# v2_0_Door.net
KiCad netlist of a schematic drawn in EAGLE
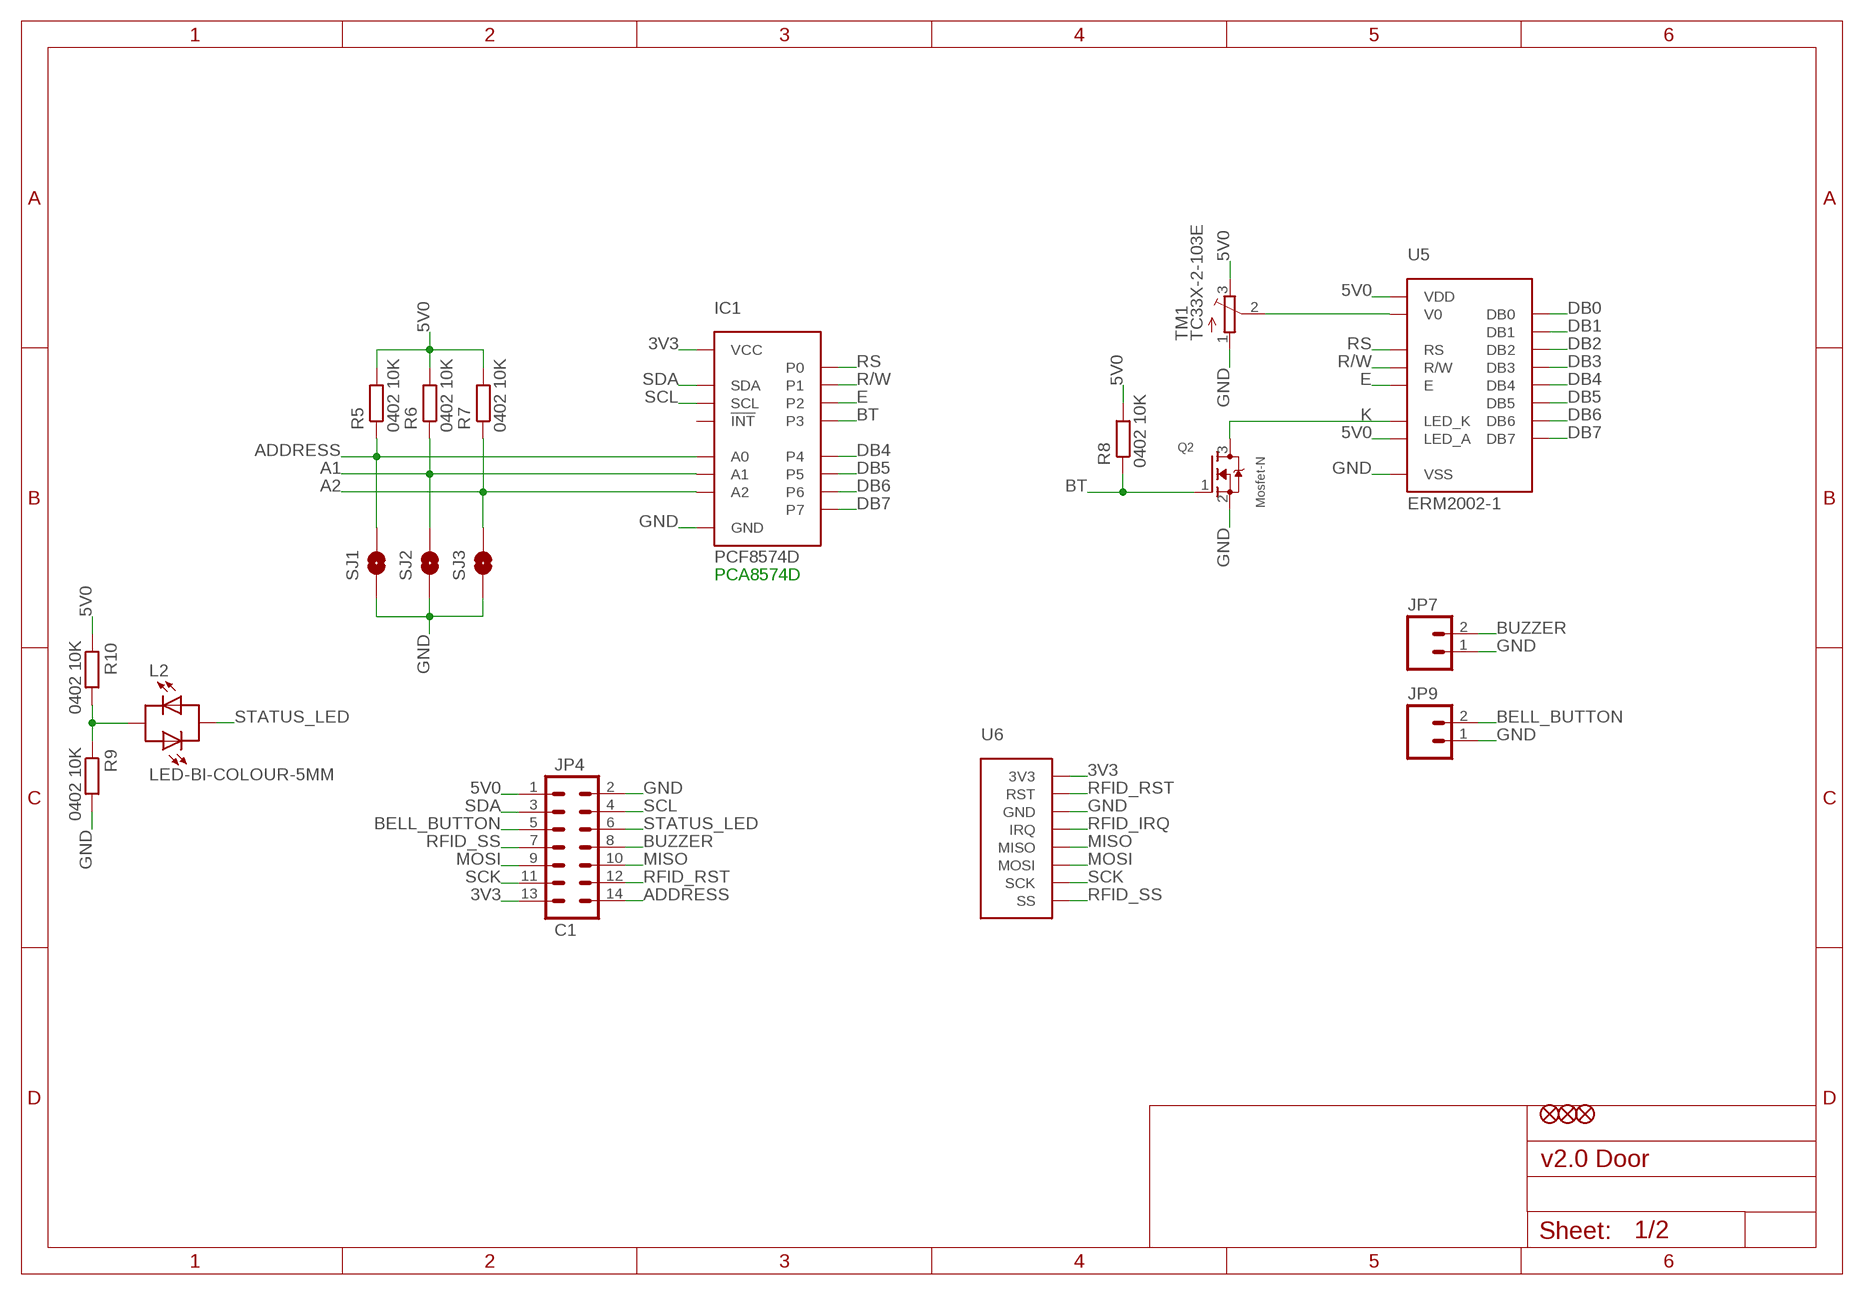
[diagram p0: schematic, sheet 1]
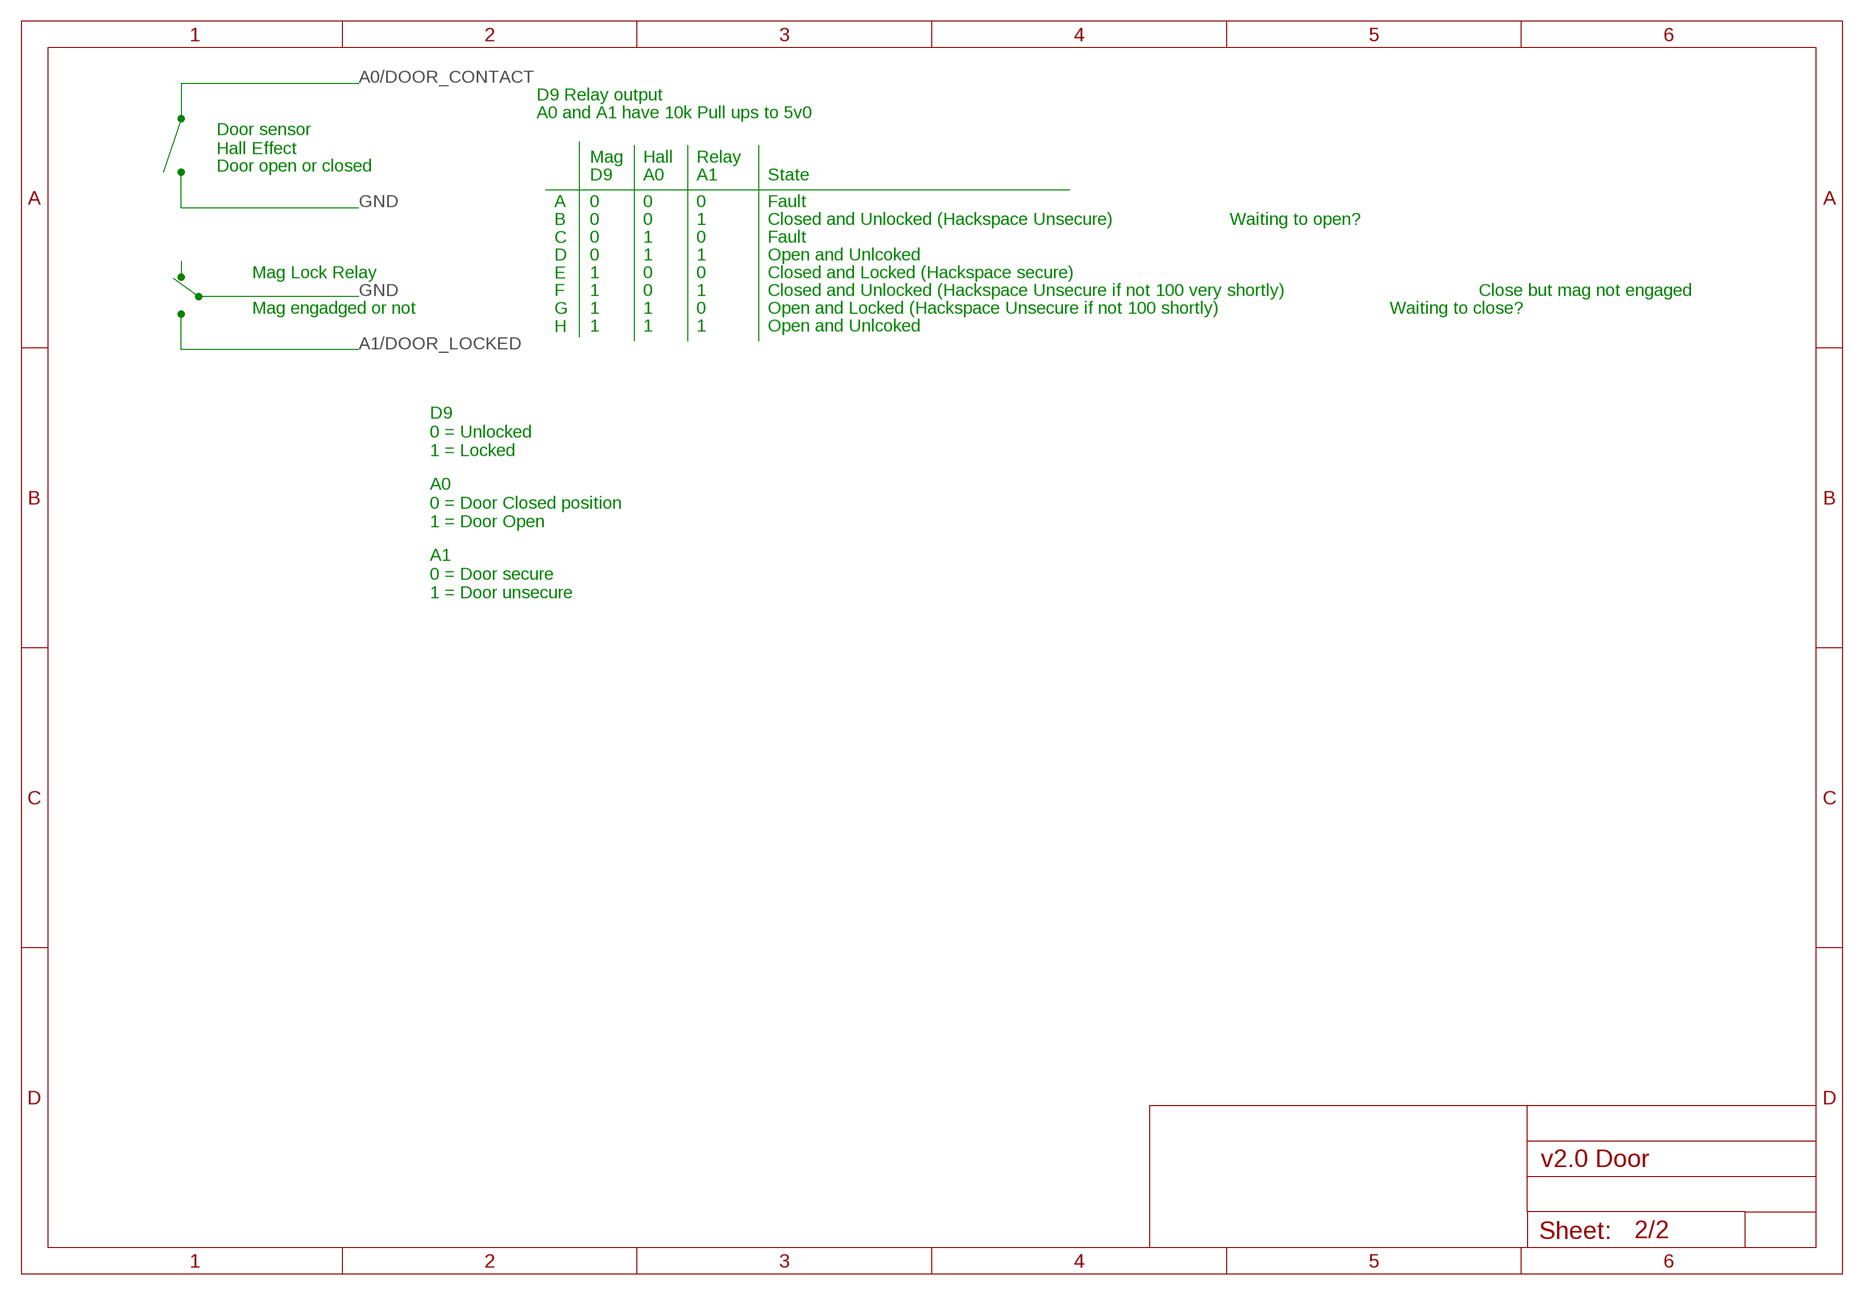
[diagram p1: schematic, sheet 2]

(export (version "E")
  (design (tool "Eeschema 10.0.6"))
  (components
    (comp (ref "IC1")
      (value "PCF8574D")
      (footprint "eagle-import:SO16")
      (libsource (lib "eagle-import") (part "PCF8574"))
    )
    (comp (ref "JP1")
      (value "FIDUCIAL1X2.5-STOP")
      (footprint "eagle-import:FIDUCIAL-1X2.5-STOP")
      (libsource (lib "eagle-import") (part "FIDUCIAL1X2.5-STOP"))
    )
    (comp (ref "JP2")
      (value "FIDUCIAL1X2.5-STOP")
      (footprint "eagle-import:FIDUCIAL-1X2.5-STOP")
      (libsource (lib "eagle-import") (part "FIDUCIAL1X2.5-STOP"))
    )
    (comp (ref "JP3")
      (value "FIDUCIAL1X2.5-STOP")
      (footprint "eagle-import:FIDUCIAL-1X2.5-STOP")
      (libsource (lib "eagle-import") (part "FIDUCIAL1X2.5-STOP"))
    )
    (comp (ref "JP4")
      (value "C1")
      (footprint "eagle-import:2X7-SHROUDED_LOCK")
      (libsource (lib "eagle-import") (part "M07X2-SHOROUDED_LOCK"))
    )
    (comp (ref "JP7")
      (value "M02POLAR_LOCK")
      (footprint "eagle-import:MOLEX-1X2_LOCK")
      (libsource (lib "eagle-import") (part "M02POLAR_LOCK"))
    )
    (comp (ref "JP9")
      (value "M02POLAR_LOCK")
      (footprint "eagle-import:MOLEX-1X2_LOCK")
      (libsource (lib "eagle-import") (part "M02POLAR_LOCK"))
    )
    (comp (ref "L2")
      (value "LED-BI-COLOUR-5MM")
      (footprint "eagle-import:LED5MM")
      (libsource (lib "eagle-import") (part "LED-BI-COLOUR-5MM"))
    )
    (comp (ref "Q2")
      (value "Mosfet-N")
      (footprint "eagle-import:SOT23-3")
      (libsource (lib "eagle-import") (part "MOSFET-N-SOT23-SPARK"))
    )
    (comp (ref "R5")
      (value "0402 10K")
      (footprint "eagle-import:R0402-SMALLER")
      (libsource (lib "eagle-import") (part "R-EU_R0402-SMALLER"))
    )
    (comp (ref "R6")
      (value "0402 10K")
      (footprint "eagle-import:R0402-SMALLER")
      (libsource (lib "eagle-import") (part "R-EU_R0402-SMALLER"))
    )
    (comp (ref "R7")
      (value "0402 10K")
      (footprint "eagle-import:R0402-SMALLER")
      (libsource (lib "eagle-import") (part "R-EU_R0402-SMALLER"))
    )
    (comp (ref "R8")
      (value "0402 10K")
      (footprint "eagle-import:R0402-SMALLER")
      (libsource (lib "eagle-import") (part "R-EU_R0402-SMALLER"))
    )
    (comp (ref "R9")
      (value "0402 10K")
      (footprint "eagle-import:R0402-SMALLER")
      (libsource (lib "eagle-import") (part "R-EU_R0402-SMALLER"))
    )
    (comp (ref "R10")
      (value "0402 10K")
      (footprint "eagle-import:R0402-SMALLER")
      (libsource (lib "eagle-import") (part "R-EU_R0402-SMALLER"))
    )
    (comp (ref "SJ1")
      (value "SOLDERJUMPERNO")
      (footprint "eagle-import:SJ_2S-NO")
      (libsource (lib "eagle-import") (part "SOLDERJUMPERNO"))
    )
    (comp (ref "SJ2")
      (value "SOLDERJUMPERNO")
      (footprint "eagle-import:SJ_2S-NO")
      (libsource (lib "eagle-import") (part "SOLDERJUMPERNO"))
    )
    (comp (ref "SJ3")
      (value "SOLDERJUMPERNO")
      (footprint "eagle-import:SJ_2S-NO")
      (libsource (lib "eagle-import") (part "SOLDERJUMPERNO"))
    )
    (comp (ref "TM1")
      (value "TC33X-2-103E")
      (footprint "eagle-import:TC33X")
      (libsource (lib "eagle-import") (part "TRIMPOTTC33X"))
    )
    (comp (ref "U5")
      (value "ERM2002-1")
      (footprint "eagle-import:ERM2002-1-GATEKEEPER")
      (libsource (lib "eagle-import") (part "ERM2002-1-GATEKEEPER"))
    )
    (comp (ref "U6")
      (value "RFID-RC522-GATEKEEPER")
      (footprint "eagle-import:RFID-RC522-GATEKEEPER")
      (libsource (lib "eagle-import") (part "RFID-RC522-GATEKEEPER"))
    )
  )
  (nets
    (net (code "1") (name "3V3") (class "Default")
      (node (ref "IC1") (pin "16") (pinfunction "VCC_16") (pintype "bidirectional"))
      (node (ref "JP4") (pin "13") (pinfunction "13_13") (pintype "passive"))
      (node (ref "U6") (pin "8") (pinfunction "3V3_8") (pintype "bidirectional"))
    )
    (net (code "2") (name "5V0") (class "Default")
      (node (ref "JP4") (pin "1") (pinfunction "1_1") (pintype "passive"))
      (node (ref "R10") (pin "1") (pinfunction "1_1") (pintype "passive"))
      (node (ref "R5") (pin "2") (pinfunction "2_2") (pintype "passive"))
      (node (ref "R6") (pin "2") (pinfunction "2_2") (pintype "passive"))
      (node (ref "R7") (pin "2") (pinfunction "2_2") (pintype "passive"))
      (node (ref "R8") (pin "2") (pinfunction "2_2") (pintype "passive"))
      (node (ref "TM1") (pin "3") (pinfunction "E_3") (pintype "passive"))
      (node (ref "U5") (pin "15") (pinfunction "LED_A_15") (pintype "bidirectional"))
      (node (ref "U5") (pin "2") (pinfunction "VDD_2") (pintype "bidirectional"))
    )
    (net (code "4") (name "A1") (class "Default")
      (node (ref "IC1") (pin "2") (pinfunction "A1_2") (pintype "bidirectional"))
      (node (ref "R6") (pin "1") (pinfunction "1_1") (pintype "passive"))
      (node (ref "SJ2") (pin "2") (pinfunction "2_2") (pintype "passive"))
    )
    (net (code "6") (name "A2") (class "Default")
      (node (ref "IC1") (pin "3") (pinfunction "A2_3") (pintype "bidirectional"))
      (node (ref "R7") (pin "1") (pinfunction "1_1") (pintype "passive"))
      (node (ref "SJ3") (pin "2") (pinfunction "2_2") (pintype "passive"))
    )
    (net (code "7") (name "ADDRESS") (class "Default")
      (node (ref "IC1") (pin "1") (pinfunction "A0_1") (pintype "bidirectional"))
      (node (ref "JP4") (pin "14") (pinfunction "14_14") (pintype "passive"))
      (node (ref "R5") (pin "1") (pinfunction "1_1") (pintype "passive"))
      (node (ref "SJ1") (pin "2") (pinfunction "2_2") (pintype "passive"))
    )
    (net (code "8") (name "BELL_BUTTON") (class "Default")
      (node (ref "JP4") (pin "5") (pinfunction "5_5") (pintype "passive"))
      (node (ref "JP9") (pin "2") (pinfunction "2_2") (pintype "passive"))
    )
    (net (code "9") (name "BT") (class "Default")
      (node (ref "IC1") (pin "7") (pinfunction "P3_7") (pintype "bidirectional"))
      (node (ref "Q2") (pin "1") (pinfunction "G_1") (pintype "bidirectional"))
      (node (ref "R8") (pin "1") (pinfunction "1_1") (pintype "passive"))
    )
    (net (code "10") (name "BUZZER") (class "Default")
      (node (ref "JP4") (pin "8") (pinfunction "8_8") (pintype "passive"))
      (node (ref "JP7") (pin "2") (pinfunction "2_2") (pintype "passive"))
    )
    (net (code "11") (name "DB0") (class "Default")
      (node (ref "U5") (pin "7") (pinfunction "DB0_7") (pintype "bidirectional"))
    )
    (net (code "12") (name "DB1") (class "Default")
      (node (ref "U5") (pin "8") (pinfunction "DB1_8") (pintype "bidirectional"))
    )
    (net (code "13") (name "DB2") (class "Default")
      (node (ref "U5") (pin "9") (pinfunction "DB2_9") (pintype "bidirectional"))
    )
    (net (code "14") (name "DB3") (class "Default")
      (node (ref "U5") (pin "10") (pinfunction "DB3_10") (pintype "bidirectional"))
    )
    (net (code "15") (name "DB4") (class "Default")
      (node (ref "IC1") (pin "9") (pinfunction "P4_9") (pintype "bidirectional"))
      (node (ref "U5") (pin "11") (pinfunction "DB4_11") (pintype "bidirectional"))
    )
    (net (code "16") (name "DB5") (class "Default")
      (node (ref "IC1") (pin "10") (pinfunction "P5_10") (pintype "bidirectional"))
      (node (ref "U5") (pin "12") (pinfunction "DB5_12") (pintype "bidirectional"))
    )
    (net (code "17") (name "DB6") (class "Default")
      (node (ref "IC1") (pin "11") (pinfunction "P6_11") (pintype "bidirectional"))
      (node (ref "U5") (pin "13") (pinfunction "DB6_13") (pintype "bidirectional"))
    )
    (net (code "18") (name "DB7") (class "Default")
      (node (ref "IC1") (pin "12") (pinfunction "P7_12") (pintype "bidirectional"))
      (node (ref "U5") (pin "14") (pinfunction "DB7_14") (pintype "bidirectional"))
    )
    (net (code "19") (name "E") (class "Default")
      (node (ref "IC1") (pin "6") (pinfunction "P2_6") (pintype "bidirectional"))
      (node (ref "U5") (pin "6") (pinfunction "E_6") (pintype "bidirectional"))
    )
    (net (code "20") (name "GND") (class "Default")
      (node (ref "IC1") (pin "8") (pinfunction "GND_8") (pintype "bidirectional"))
      (node (ref "JP4") (pin "2") (pinfunction "2_2") (pintype "passive"))
      (node (ref "JP7") (pin "1") (pinfunction "1_1") (pintype "passive"))
      (node (ref "JP9") (pin "1") (pinfunction "1_1") (pintype "passive"))
      (node (ref "Q2") (pin "2") (pinfunction "S_2") (pintype "bidirectional"))
      (node (ref "R9") (pin "2") (pinfunction "2_2") (pintype "passive"))
      (node (ref "SJ1") (pin "1") (pinfunction "1_1") (pintype "passive"))
      (node (ref "SJ2") (pin "1") (pinfunction "1_1") (pintype "passive"))
      (node (ref "SJ3") (pin "1") (pinfunction "1_1") (pintype "passive"))
      (node (ref "TM1") (pin "1") (pinfunction "A_1") (pintype "passive"))
      (node (ref "U5") (pin "1") (pinfunction "VSS_1") (pintype "bidirectional"))
      (node (ref "U6") (pin "6") (pinfunction "GND_6") (pintype "bidirectional"))
    )
    (net (code "21") (name "K") (class "Default")
      (node (ref "Q2") (pin "3") (pinfunction "D_3") (pintype "bidirectional"))
      (node (ref "U5") (pin "16") (pinfunction "LED_K_16") (pintype "bidirectional"))
    )
    (net (code "22") (name "MISO") (class "Default")
      (node (ref "JP4") (pin "10") (pinfunction "10_10") (pintype "passive"))
      (node (ref "U6") (pin "4") (pinfunction "MISO_4") (pintype "bidirectional"))
    )
    (net (code "23") (name "MOSI") (class "Default")
      (node (ref "JP4") (pin "9") (pinfunction "9_9") (pintype "passive"))
      (node (ref "U6") (pin "3") (pinfunction "MOSI_3") (pintype "bidirectional"))
    )
    (net (code "25") (name "Net-(L2-1)") (class "Default")
      (node (ref "L2") (pin "A") (pinfunction "1_A") (pintype "passive"))
      (node (ref "R10") (pin "2") (pinfunction "2_2") (pintype "passive"))
      (node (ref "R9") (pin "1") (pinfunction "1_1") (pintype "passive"))
    )
    (net (code "26") (name "Net-(TM1-S)") (class "Default")
      (node (ref "TM1") (pin "2") (pinfunction "S_2") (pintype "passive"))
      (node (ref "U5") (pin "3") (pinfunction "V0_3") (pintype "bidirectional"))
    )
    (net (code "27") (name "RFID_IRQ") (class "Default")
      (node (ref "U6") (pin "5") (pinfunction "IRQ_5") (pintype "bidirectional"))
    )
    (net (code "28") (name "RFID_RST") (class "Default")
      (node (ref "JP4") (pin "12") (pinfunction "12_12") (pintype "passive"))
      (node (ref "U6") (pin "7") (pinfunction "RST_7") (pintype "bidirectional"))
    )
    (net (code "29") (name "RFID_SS") (class "Default")
      (node (ref "JP4") (pin "7") (pinfunction "7_7") (pintype "passive"))
      (node (ref "U6") (pin "1") (pinfunction "SS_1") (pintype "bidirectional"))
    )
    (net (code "30") (name "RS") (class "Default")
      (node (ref "IC1") (pin "4") (pinfunction "P0_4") (pintype "bidirectional"))
      (node (ref "U5") (pin "4") (pinfunction "RS_4") (pintype "bidirectional"))
    )
    (net (code "31") (name "R{slash}W") (class "Default")
      (node (ref "IC1") (pin "5") (pinfunction "P1_5") (pintype "bidirectional"))
      (node (ref "U5") (pin "5") (pinfunction "R/W_5") (pintype "bidirectional"))
    )
    (net (code "32") (name "SCK") (class "Default")
      (node (ref "JP4") (pin "11") (pinfunction "11_11") (pintype "passive"))
      (node (ref "U6") (pin "2") (pinfunction "SCK_2") (pintype "bidirectional"))
    )
    (net (code "33") (name "SCL") (class "Default")
      (node (ref "IC1") (pin "14") (pinfunction "SCL_14") (pintype "bidirectional"))
      (node (ref "JP4") (pin "4") (pinfunction "4_4") (pintype "passive"))
    )
    (net (code "34") (name "SDA") (class "Default")
      (node (ref "IC1") (pin "15") (pinfunction "SDA_15") (pintype "bidirectional"))
      (node (ref "JP4") (pin "3") (pinfunction "3_3") (pintype "passive"))
    )
    (net (code "35") (name "STATUS_LED") (class "Default")
      (node (ref "JP4") (pin "6") (pinfunction "6_6") (pintype "passive"))
      (node (ref "L2") (pin "K") (pinfunction "2_K") (pintype "passive"))
    )
    (net (code "36") (name "unconnected-(IC1-~{INT}-Pad13)") (class "Default")
      (node (ref "IC1") (pin "13") (pinfunction "~{INT}_13") (pintype "bidirectional"))
    )
  )
)
